# ADC.net
KiCad netlist of a schematic drawn in Altium Designer
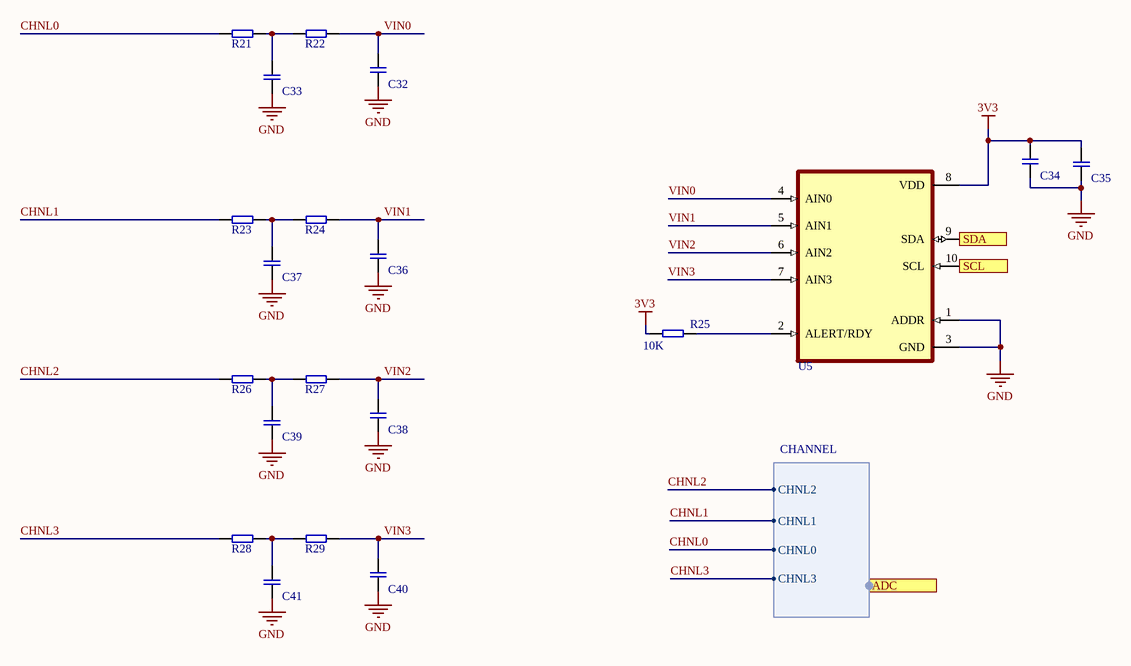
[diagram p0: ADC.SchDoc]

(export (version "E")
  (design (tool "Eeschema 10.0.6"))
  (components
    (comp (ref "C32")
      (value "0.1uF")
      (footprint "C0603")
      (description "CAP CER 0.1UF 16V X7R 0603")
      (fields (field (name "PART NUMBER") "C0603C104J4RACTU") (field (name "VOLTAGE") "16V"))
      (libsource (lib "anayurt") (part "CAP"))
    )
    (comp (ref "C33")
      (value "0.1uF")
      (footprint "C0603")
      (description "CAP CER 0.1UF 16V X7R 0603")
      (fields (field (name "PART NUMBER") "C0603C104J4RACTU") (field (name "VOLTAGE") "16V"))
      (libsource (lib "anayurt") (part "CAP"))
    )
    (comp (ref "C34")
      (value "1uF")
      (footprint "C0603")
      (description "CAP CER 1UF 16V X5R 0603")
      (fields (field (name "PART NUMBER") "GMC10X5R105K16NT") (field (name "VOLTAGE") "16V"))
      (libsource (lib "anayurt") (part "CAP"))
    )
    (comp (ref "C35")
      (value "10uF")
      (footprint "C0603")
      (description "CAP CER 10UF 16V X5R 0603")
      (fields (field (name "PART NUMBER") "GRT188R61C106KE13D") (field (name "VOLTAGE") "16V"))
      (libsource (lib "anayurt") (part "CAP"))
    )
    (comp (ref "C36")
      (value "0.1uF")
      (footprint "C0603")
      (description "CAP CER 0.1UF 16V X7R 0603")
      (fields (field (name "PART NUMBER") "C0603C104J4RACTU") (field (name "VOLTAGE") "16V"))
      (libsource (lib "anayurt") (part "CAP"))
    )
    (comp (ref "C37")
      (value "0.1uF")
      (footprint "C0603")
      (description "CAP CER 0.1UF 16V X7R 0603")
      (fields (field (name "PART NUMBER") "C0603C104J4RACTU") (field (name "VOLTAGE") "16V"))
      (libsource (lib "anayurt") (part "CAP"))
    )
    (comp (ref "C38")
      (value "0.1uF")
      (footprint "C0603")
      (description "CAP CER 0.1UF 16V X7R 0603")
      (fields (field (name "PART NUMBER") "C0603C104J4RACTU") (field (name "VOLTAGE") "16V"))
      (libsource (lib "anayurt") (part "CAP"))
    )
    (comp (ref "C39")
      (value "0.1uF")
      (footprint "C0603")
      (description "CAP CER 0.1UF 16V X7R 0603")
      (fields (field (name "PART NUMBER") "C0603C104J4RACTU") (field (name "VOLTAGE") "16V"))
      (libsource (lib "anayurt") (part "CAP"))
    )
    (comp (ref "C40")
      (value "0.1uF")
      (footprint "C0603")
      (description "CAP CER 0.1UF 16V X7R 0603")
      (fields (field (name "PART NUMBER") "C0603C104J4RACTU") (field (name "VOLTAGE") "16V"))
      (libsource (lib "anayurt") (part "CAP"))
    )
    (comp (ref "C41")
      (value "0.1uF")
      (footprint "C0603")
      (description "CAP CER 0.1UF 16V X7R 0603")
      (fields (field (name "PART NUMBER") "C0603C104J4RACTU") (field (name "VOLTAGE") "16V"))
      (libsource (lib "anayurt") (part "CAP"))
    )
    (comp (ref "R21")
      (value "0R")
      (footprint "R0402")
      (description "RES 0 OHM JUMPER 1/16W 0402")
      (fields (field (name "PART NUMBER") "RMCF0402ZT0R00") (field (name "TOLERANCE") "1%"))
      (libsource (lib "anayurt") (part "RES"))
    )
    (comp (ref "R22")
      (value "0R")
      (footprint "R0402")
      (description "RES 0 OHM JUMPER 1/16W 0402")
      (fields (field (name "PART NUMBER") "RMCF0402ZT0R00") (field (name "TOLERANCE") "1%"))
      (libsource (lib "anayurt") (part "RES"))
    )
    (comp (ref "R23")
      (value "0R")
      (footprint "R0402")
      (description "RES 0 OHM JUMPER 1/16W 0402")
      (fields (field (name "PART NUMBER") "RMCF0402ZT0R00") (field (name "TOLERANCE") "1%"))
      (libsource (lib "anayurt") (part "RES"))
    )
    (comp (ref "R24")
      (value "0R")
      (footprint "R0402")
      (description "RES 0 OHM JUMPER 1/16W 0402")
      (fields (field (name "PART NUMBER") "RMCF0402ZT0R00") (field (name "TOLERANCE") "1%"))
      (libsource (lib "anayurt") (part "RES"))
    )
    (comp (ref "R25")
      (value "10K")
      (footprint "R0603")
      (description "RES 10K OHM 1% 1/10W 0603")
      (fields (field (name "PART NUMBER") "RMCF0603FT10K0") (field (name "TOLERANCE") "1%"))
      (libsource (lib "anayurt") (part "RES"))
    )
    (comp (ref "R26")
      (value "0R")
      (footprint "R0402")
      (description "RES 0 OHM JUMPER 1/16W 0402")
      (fields (field (name "PART NUMBER") "RMCF0402ZT0R00") (field (name "TOLERANCE") "1%"))
      (libsource (lib "anayurt") (part "RES"))
    )
    (comp (ref "R27")
      (value "0R")
      (footprint "R0402")
      (description "RES 0 OHM JUMPER 1/16W 0402")
      (fields (field (name "PART NUMBER") "RMCF0402ZT0R00") (field (name "TOLERANCE") "1%"))
      (libsource (lib "anayurt") (part "RES"))
    )
    (comp (ref "R28")
      (value "0R")
      (footprint "R0402")
      (description "RES 0 OHM JUMPER 1/16W 0402")
      (fields (field (name "PART NUMBER") "RMCF0402ZT0R00") (field (name "TOLERANCE") "1%"))
      (libsource (lib "anayurt") (part "RES"))
    )
    (comp (ref "R29")
      (value "0R")
      (footprint "R0402")
      (description "RES 0 OHM JUMPER 1/16W 0402")
      (fields (field (name "PART NUMBER") "RMCF0402ZT0R00") (field (name "TOLERANCE") "1%"))
      (libsource (lib "anayurt") (part "RES"))
    )
    (comp (ref "U5")
      (value "ADS1115IDGST")
      (footprint "ADS1115IDGST")
      (description "IC ADC 16BIT SIGMA-DELTA 10VSSOP")
      (fields (field (name "MANUFACTURER") "Texas Instruments"))
      (libsource (lib "anayurt") (part "ADS1115IDGST"))
    )
  )
  (nets
    (net (code "2") (name "/CHNL0") (class "Default")
      (node (ref "R21") (pin "1") (pinfunction "1_1") (pintype "passive"))
    )
    (net (code "3") (name "/CHNL1") (class "Default")
      (node (ref "R23") (pin "1") (pinfunction "1_1") (pintype "passive"))
    )
    (net (code "4") (name "/CHNL2") (class "Default")
      (node (ref "R26") (pin "1") (pinfunction "1_1") (pintype "passive"))
    )
    (net (code "5") (name "/CHNL3") (class "Default")
      (node (ref "R28") (pin "1") (pinfunction "1_1") (pintype "passive"))
    )
    (net (code "6") (name "/SCL") (class "Default")
      (node (ref "U5") (pin "10") (pinfunction "SCL_10") (pintype "input"))
    )
    (net (code "7") (name "/SDA") (class "Default")
      (node (ref "U5") (pin "9") (pinfunction "SDA_9") (pintype "bidirectional"))
    )
    (net (code "8") (name "/VIN0") (class "Default")
      (node (ref "C32") (pin "1") (pinfunction "1_1") (pintype "passive"))
      (node (ref "R22") (pin "2") (pinfunction "2_2") (pintype "passive"))
      (node (ref "U5") (pin "4") (pinfunction "AIN0_4") (pintype "input"))
    )
    (net (code "9") (name "/VIN1") (class "Default")
      (node (ref "C36") (pin "1") (pinfunction "1_1") (pintype "passive"))
      (node (ref "R24") (pin "2") (pinfunction "2_2") (pintype "passive"))
      (node (ref "U5") (pin "5") (pinfunction "AIN1_5") (pintype "input"))
    )
    (net (code "10") (name "/VIN2") (class "Default")
      (node (ref "C38") (pin "1") (pinfunction "1_1") (pintype "passive"))
      (node (ref "R27") (pin "2") (pinfunction "2_2") (pintype "passive"))
      (node (ref "U5") (pin "6") (pinfunction "AIN2_6") (pintype "input"))
    )
    (net (code "11") (name "/VIN3") (class "Default")
      (node (ref "C40") (pin "1") (pinfunction "1_1") (pintype "passive"))
      (node (ref "R29") (pin "2") (pinfunction "2_2") (pintype "passive"))
      (node (ref "U5") (pin "7") (pinfunction "AIN3_7") (pintype "input"))
    )
    (net (code "13") (name "3V3") (class "Default")
      (node (ref "C34") (pin "2") (pinfunction "2_2") (pintype "passive"))
      (node (ref "C35") (pin "2") (pinfunction "2_2") (pintype "passive"))
      (node (ref "R25") (pin "1") (pinfunction "1_1") (pintype "passive"))
      (node (ref "U5") (pin "8") (pinfunction "VDD_8") (pintype "power_in"))
    )
    (net (code "14") (name "GND") (class "Default")
      (node (ref "C32") (pin "2") (pinfunction "2_2") (pintype "passive"))
      (node (ref "C33") (pin "1") (pinfunction "1_1") (pintype "passive"))
      (node (ref "C34") (pin "1") (pinfunction "1_1") (pintype "passive"))
      (node (ref "C35") (pin "1") (pinfunction "1_1") (pintype "passive"))
      (node (ref "C36") (pin "2") (pinfunction "2_2") (pintype "passive"))
      (node (ref "C37") (pin "1") (pinfunction "1_1") (pintype "passive"))
      (node (ref "C38") (pin "2") (pinfunction "2_2") (pintype "passive"))
      (node (ref "C39") (pin "1") (pinfunction "1_1") (pintype "passive"))
      (node (ref "C40") (pin "2") (pinfunction "2_2") (pintype "passive"))
      (node (ref "C41") (pin "1") (pinfunction "1_1") (pintype "passive"))
      (node (ref "U5") (pin "1") (pinfunction "ADDR_1") (pintype "input"))
      (node (ref "U5") (pin "3") (pinfunction "GND_3") (pintype "power_in"))
    )
    (net (code "15") (name "Net-(C33-Pad2)") (class "Default")
      (node (ref "C33") (pin "2") (pinfunction "2_2") (pintype "passive"))
      (node (ref "R21") (pin "2") (pinfunction "2_2") (pintype "passive"))
      (node (ref "R22") (pin "1") (pinfunction "1_1") (pintype "passive"))
    )
    (net (code "16") (name "Net-(C37-Pad2)") (class "Default")
      (node (ref "C37") (pin "2") (pinfunction "2_2") (pintype "passive"))
      (node (ref "R23") (pin "2") (pinfunction "2_2") (pintype "passive"))
      (node (ref "R24") (pin "1") (pinfunction "1_1") (pintype "passive"))
    )
    (net (code "17") (name "Net-(C39-Pad2)") (class "Default")
      (node (ref "C39") (pin "2") (pinfunction "2_2") (pintype "passive"))
      (node (ref "R26") (pin "2") (pinfunction "2_2") (pintype "passive"))
      (node (ref "R27") (pin "1") (pinfunction "1_1") (pintype "passive"))
    )
    (net (code "18") (name "Net-(C41-Pad2)") (class "Default")
      (node (ref "C41") (pin "2") (pinfunction "2_2") (pintype "passive"))
      (node (ref "R28") (pin "2") (pinfunction "2_2") (pintype "passive"))
      (node (ref "R29") (pin "1") (pinfunction "1_1") (pintype "passive"))
    )
    (net (code "19") (name "Net-(U5-ALERT{slash}RDY)") (class "Default")
      (node (ref "R25") (pin "2") (pinfunction "2_2") (pintype "passive"))
      (node (ref "U5") (pin "2") (pinfunction "ALERT/RDY_2") (pintype "input"))
    )
  )
)
